# OSCILLATEUR.net
KiCad netlist of a schematic drawn in Altium Designer
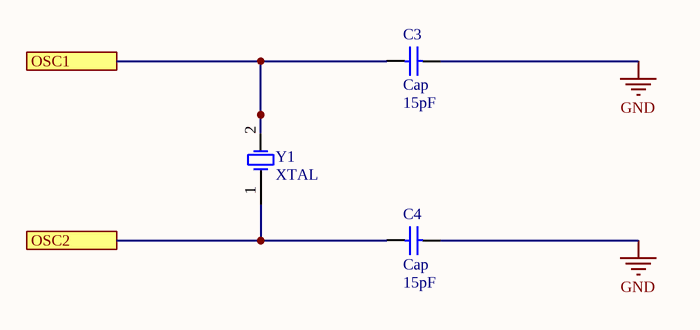
[diagram p0: OSCILLATEUR.SchDoc]

(export (version "E")
  (design (tool "Eeschema 10.0.6"))
  (components
    (comp (ref "C3")
      (value "Cap")
      (footprint "RAD-0.2")
      (description "Capacitor")
      (fields (field (name "ALTIUM_VALUE") "15pF") (field (name "PUBLISHER") "Altium Limited"))
      (libsource (lib "Miscellaneous Devices") (part "Cap"))
    )
    (comp (ref "C4")
      (value "Cap")
      (footprint "RAD-0.2")
      (description "Capacitor")
      (fields (field (name "ALTIUM_VALUE") "15pF") (field (name "PUBLISHER") "Altium Limited"))
      (libsource (lib "Miscellaneous Devices") (part "Cap"))
    )
    (comp (ref "Y1")
      (value "XTAL")
      (footprint "R38")
      (description "Crystal Oscillator")
      (fields (field (name "PUBLISHER") "Altium Limited"))
      (libsource (lib "Miscellaneous Devices") (part "XTAL"))
    )
  )
  (nets
    (net (code "1") (name "/OSC1") (class "Default")
      (node (ref "C3") (pin "1") (pinfunction "1_1") (pintype "passive"))
      (node (ref "Y1") (pin "2") (pinfunction "OSC2_2") (pintype "passive"))
    )
    (net (code "2") (name "/OSC2") (class "Default")
      (node (ref "C4") (pin "1") (pinfunction "1_1") (pintype "passive"))
      (node (ref "Y1") (pin "1") (pinfunction "OSC1_1") (pintype "passive"))
    )
    (net (code "3") (name "GND") (class "Default")
      (node (ref "C3") (pin "2") (pinfunction "2_2") (pintype "passive"))
      (node (ref "C4") (pin "2") (pinfunction "2_2") (pintype "passive"))
    )
  )
)
